# PoE_Si3404.net
KiCad netlist of a schematic drawn in Altium Designer
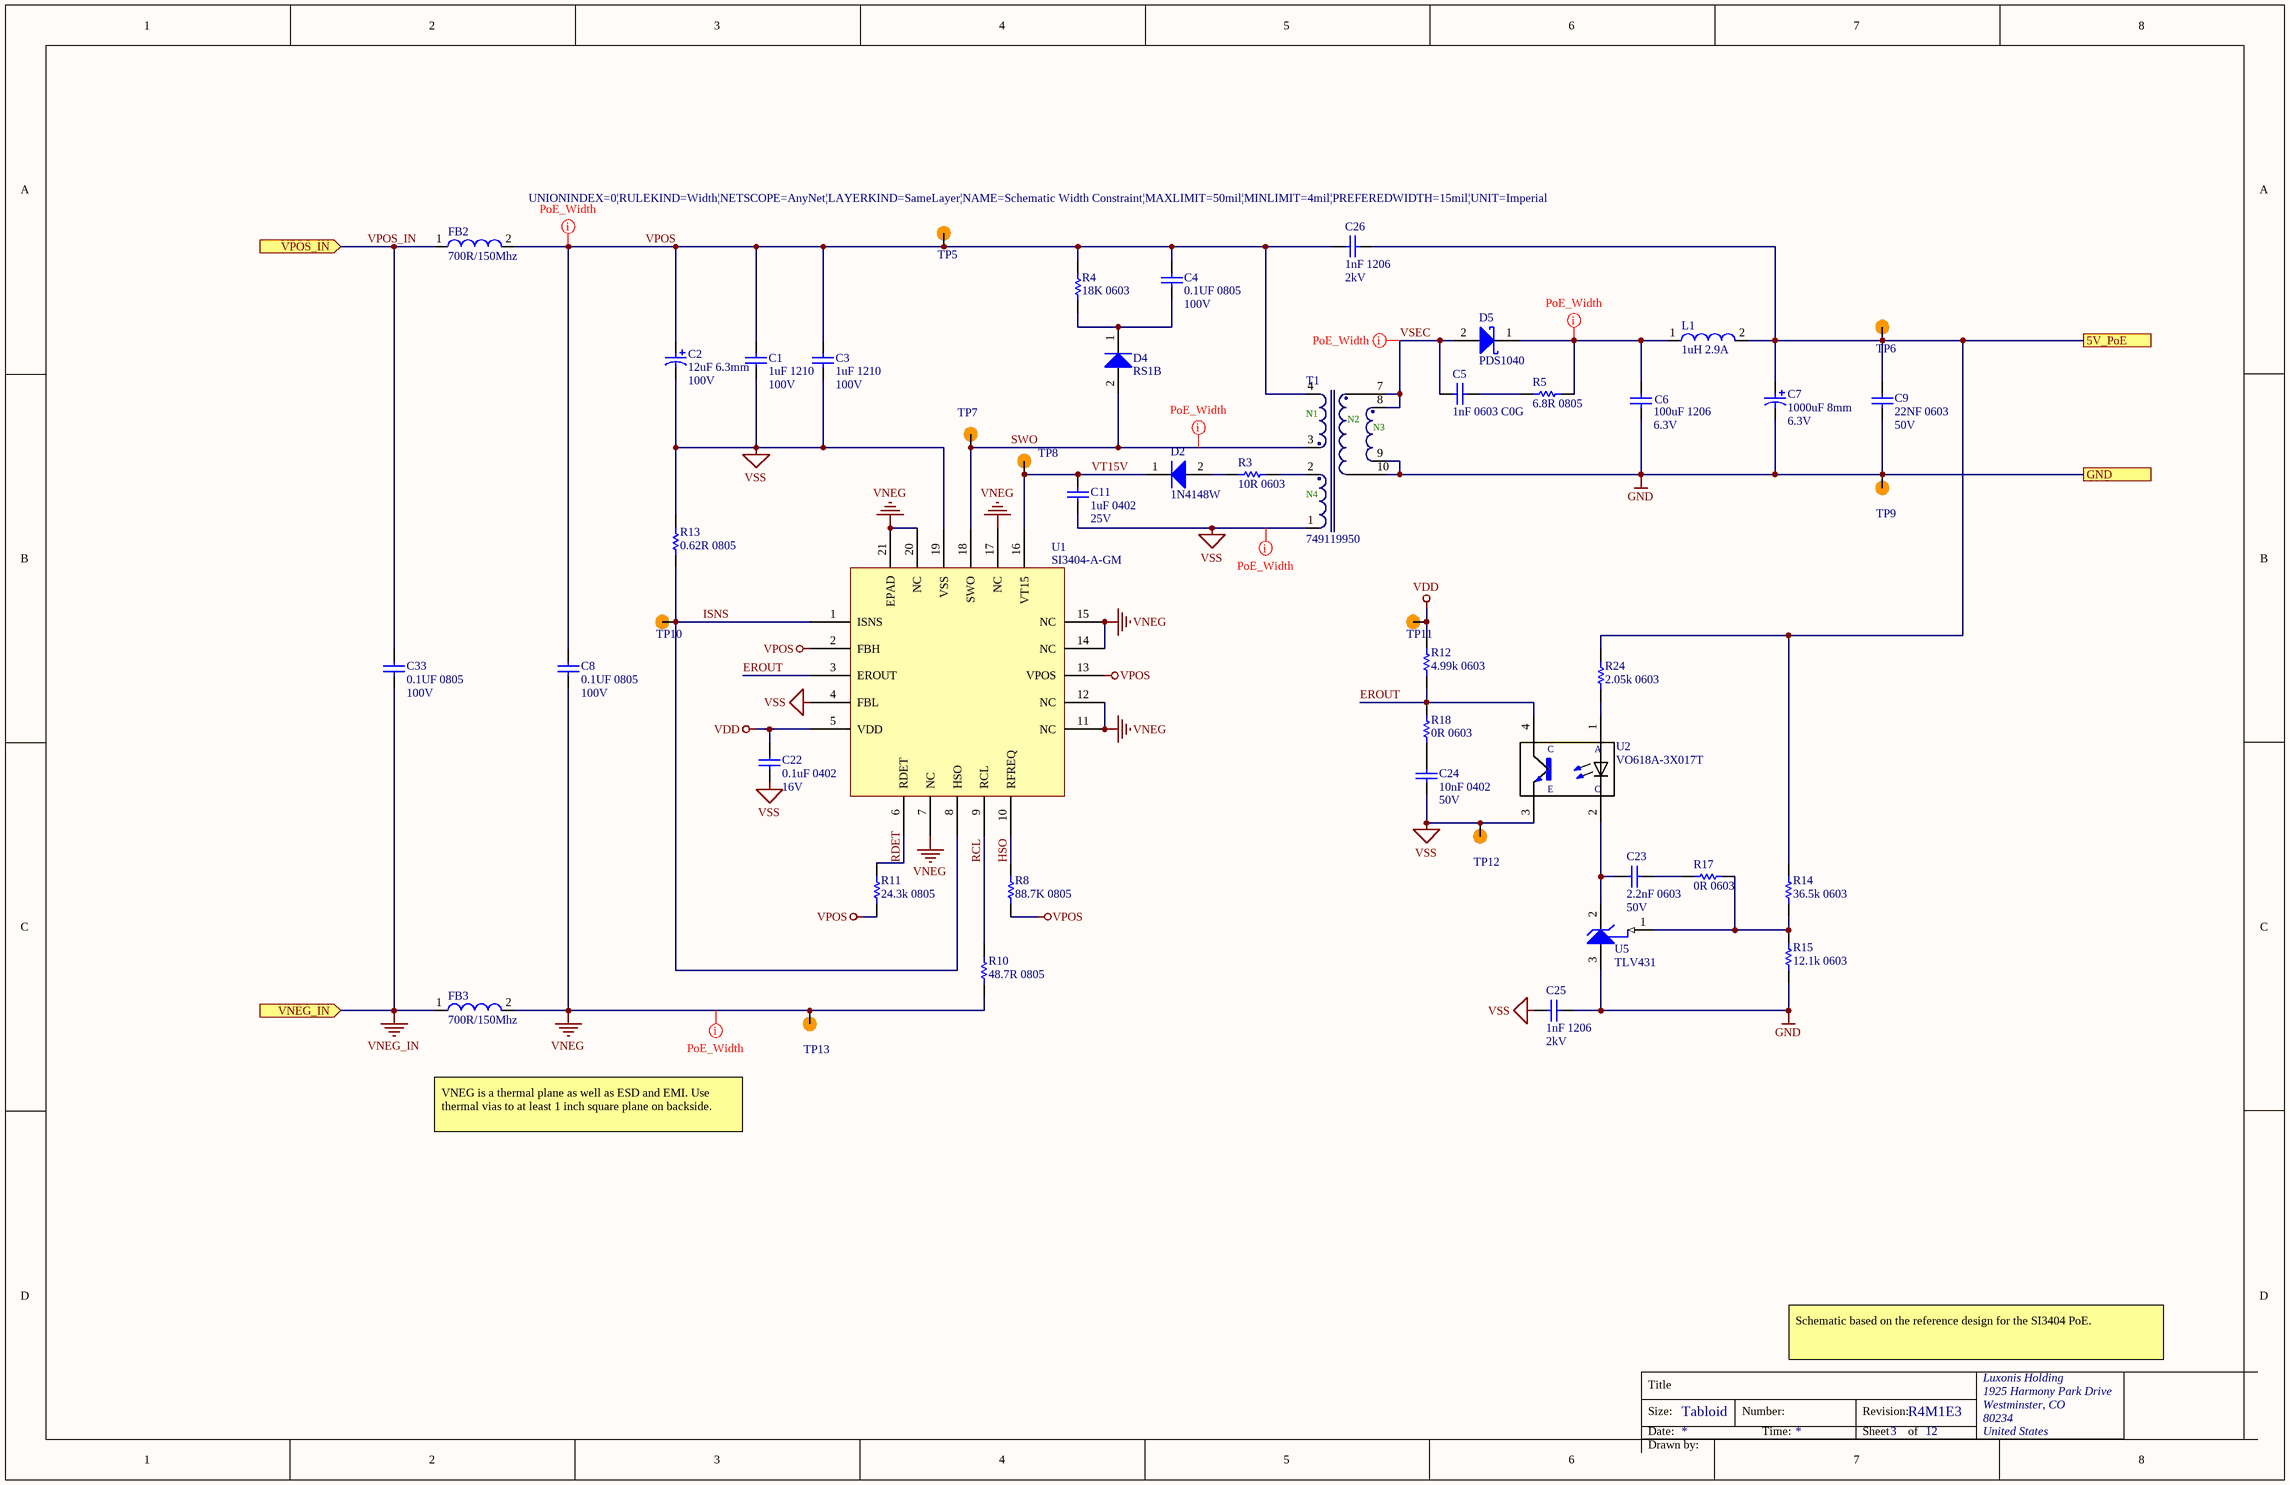
[diagram p0: PoE_Si3404.SchDoc]

(export (version "E")
  (design (tool "Eeschema 10.0.6"))
  (components
    (comp (ref "C1")
      (value "1uF 1210")
      (footprint "CAP_Altium_Vault_Generic:CAPC1210(3225)280_N")
      (description "CAP CER 1UF 100V X7R 1210")
      (fields (field (name "TOLERANCE") "10%") (field (name "VOLTAGE RATING") "100V"))
      (libsource (lib "PCBProject") (part "CL32B105KCJNNNE"))
    )
    (comp (ref "C2")
      (value "12uF 6.3mm")
      (footprint "BW2098POE:EEU-FC2A120")
      (description "CAP ALUM 12UF 20% 100V RADIAL")
      (fields (field (name "TOLERANCE") "20%") (field (name "VOLTAGE") "100V"))
      (libsource (lib "BW2098POE") (part "EEU-FC2A120"))
    )
    (comp (ref "C3")
      (value "1uF 1210")
      (footprint "CAP_Altium_Vault_Generic:CAPC1210(3225)280_N")
      (description "CAP CER 1UF 100V X7R 1210")
      (fields (field (name "TOLERANCE") "10%") (field (name "VOLTAGE RATING") "100V"))
      (libsource (lib "PCBProject") (part "CL32B105KCJNNNE"))
    )
    (comp (ref "C4")
      (value "0.1UF 0805")
      (footprint "CAP_Altium_Vault_Generic:CAPC0805(2012)145_N")
      (description "CAP CER 0.1UF 100V X7R 0805")
      (fields (field (name "TOLERANCE") "10%") (field (name "VOLTAGE RATING") "100V"))
      (libsource (lib "BW2098POE") (part "CL21B104KCFNNNE"))
    )
    (comp (ref "C5")
      (value "1nF 0603 C0G")
      (footprint "CAP_Altium_Vault_Generic:CAPC0603(1608)100_N")
      (description "CAP CER 1000PF 50V C0G/NP0 0603")
      (fields
        (field (name "MANUFACTURER") "Murata")
        (field (name "MANUFACTURER PART NUMBER") "GRM1885C1H102FA01D")
      )
      (libsource (lib "LuxonisMaster") (part "GRM1885C1H102FA01D"))
    )
    (comp (ref "C6")
      (value "100uF 1206")
      (footprint "CAP_Altium_Vault_Generic:CAPC1206(3216)190_N")
      (description "CAP CER 100UF 6.3V X5R 1206")
      (fields (field (name "TOLERANCE") "20%") (field (name "VOLTAGE") "6.3V"))
      (libsource (lib "PCBProject") (part "CL31A107MQHNNNE"))
    )
    (comp (ref "C7")
      (value "1000uF 8mm")
      (footprint "BW2098POE:ECA-0JM102")
      (description "CAP ALUM 1000UF 20% 6.3V RADIAL")
      (fields (field (name "TOLERANCE") "20%") (field (name "VOLTAGE") "6.3V"))
      (libsource (lib "BW2098POE") (part "ECA-0JM102"))
    )
    (comp (ref "C8")
      (value "0.1UF 0805")
      (footprint "CAP_Altium_Vault_Generic:CAPC0805(2012)145_N")
      (description "CAP CER 0.1UF 100V X7R 0805")
      (fields (field (name "TOLERANCE") "10%") (field (name "VOLTAGE RATING") "100V"))
      (libsource (lib "PCBProject") (part "CL21B104KCFNNNE"))
    )
    (comp (ref "C9")
      (value "22NF 0603")
      (footprint "CAP_Altium_Vault_Generic:CAPC0603(1608)100_N")
      (description "CAP CER 0.022UF 50V X7R 0603")
      (fields (field (name "TOLERANCE") "10%") (field (name "VOLTAGE") "50V"))
      (libsource (lib "LuxonisMaster") (part "C0603C223K5RACTU"))
    )
    (comp (ref "C11")
      (value "1uF 0402")
      (footprint "CAP_Altium_Vault_Generic:CAPC0402(1005)70_N")
      (description "CAP CER 1UF 25V X5R 0402 10%")
      (fields
        (field (name "TOLERANCE") "10%")
        (field (name "VOLTAGE") "25V")
        (field (name "VOLTAGE RATING") "25V")
      )
      (libsource (lib "LuxonisMaster") (part "GRM155R61E105KA12D"))
    )
    (comp (ref "C22")
      (value "0.1uF 0402")
      (footprint "CAP_Altium_Vault_Generic:CAPC0402(1005)60_N")
      (description "CAP CER 0.1UF 16V X7R 0402")
      (fields (field (name "TOLERANCE") "10%") (field (name "VOLTAGE RATING") "16V"))
      (libsource (lib "PCBProject") (part "CL05B104KO5NFNC"))
    )
    (comp (ref "C23")
      (value "2.2nF 0603")
      (footprint "CAP_Altium_Vault_Generic:CAPC0603(1608)100_N")
      (description "CAP CER 2200PF 50V C0G/NP0 0603")
      (fields (field (name "TOLERANCE") "5%") (field (name "VOLTAGE") "50V"))
      (libsource (lib "BW2098POE") (part "GRM1885C1H222JA01D"))
    )
    (comp (ref "C24")
      (value "10nF 0402")
      (footprint "CAP_Altium_Vault_Generic:CAPC0402(1005)60_N")
      (description "CAP CER 10000PF 50V X7R 0402")
      (fields
        (field (name "TOLERANCE") "10%")
        (field (name "VOLTAGE") "25V")
        (field (name "VOLTAGE RATING") "50V")
      )
      (libsource (lib "LuxonisMaster") (part "GRM155R71H103KA88D"))
    )
    (comp (ref "C25")
      (value "1nF 1206")
      (footprint "CAP_Altium_Vault_Generic:CAPC1206(3216)190_N")
      (description "CAP CER 1000PF 2KV X7R 1206")
      (fields (field (name "TOLERANCE") "10%") (field (name "VOLTAGE RATING (DC)") "2kV"))
      (libsource (lib "PCBProject") (part "C1206C102KGRACTU"))
    )
    (comp (ref "C26")
      (value "1nF 1206")
      (footprint "CAP_Altium_Vault_Generic:CAPC1206(3216)190_N")
      (description "CAP CER 1000PF 2KV X7R 1206")
      (fields (field (name "TOLERANCE") "10%") (field (name "VOLTAGE RATING (DC)") "2kV"))
      (libsource (lib "PCBProject") (part "C1206C102KGRACTU"))
    )
    (comp (ref "C33")
      (value "0.1UF 0805")
      (footprint "CAP_Altium_Vault_Generic:CAPC0805(2012)145_N")
      (description "CAP CER 0.1UF 100V X7R 0805")
      (fields (field (name "TOLERANCE") "10%") (field (name "VOLTAGE RATING") "100V"))
      (libsource (lib "PCBProject") (part "CL21B104KCFNNNE"))
    )
    (comp (ref "D2")
      (value "1N4148W")
      (footprint "BW2098POE:1N4148W-7-F")
      (description "DIODE GEN PURP 100V 300MA SOD123")
      (fields (field (name "VOLTAGE") "100V"))
      (libsource (lib "PCBProject") (part "1N4148W-7-F"))
    )
    (comp (ref "D4")
      (value "RS1B")
      (footprint "BW2098POE:RS1B")
      (description "DIODE GEN PURP 100V 1A SMA")
      (libsource (lib "BW2098POE") (part "RS1B"))
    )
    (comp (ref "D5")
      (value "PDS1040")
      (footprint "BW2098POE:PDS1040-13")
      (description "DIODE SCHOTTKY 40V 10A POWERDI5")
      (libsource (lib "PCBProject") (part "PDS1040-13"))
    )
    (comp (ref "FB2")
      (value "700R/150Mhz")
      (footprint "BW2098POE:742792040")
      (description "FERRITE BEAD 600 OHM 0805 1LN")
      (fields (field (name "TOLERANCE") "25%"))
      (libsource (lib "BW2098POE") (part "742792040"))
    )
    (comp (ref "FB3")
      (value "700R/150Mhz")
      (footprint "BW2098POE:742792040")
      (description "FERRITE BEAD 600 OHM 0805 1LN")
      (fields (field (name "TOLERANCE") "25%"))
      (libsource (lib "BW2098POE") (part "742792040"))
    )
    (comp (ref "L1")
      (value "1uH 2.9A")
      (footprint "BW2098POE:DO1608C-102MLx")
      (description "IND POWER WIREWOUND 1uH 20% 100KHz FERRITE 2.7A")
      (fields (field (name "TOLERANCE") "20%"))
      (libsource (lib "PCBProject") (part "DO1608C-102ML"))
    )
    (comp (ref "R3")
      (value "10R 0603")
      (footprint "RES_Altium_Vault_Generic:RESC0603(1608)_N")
      (description "RES SMD 10 OHM 1% 1/10W 0603")
      (fields (field (name "TOLERANCE") "1%"))
      (libsource (lib "PCBProject") (part "CRCW060310R0FKEA"))
    )
    (comp (ref "R4")
      (value "18K 0603")
      (footprint "RES_Altium_Vault_Generic:RESC0603(1608)_N")
      (description "RES SMD 18K OHM 5% 1/10W 0603")
      (fields (field (name "TOLERANCE") "5%"))
      (libsource (lib "BW2098POE") (part "RC0603JR-0718KL"))
    )
    (comp (ref "R5")
      (value "6.8R 0805")
      (footprint "RES_Altium_Vault_Generic:RESC0805(2012)_N")
      (description "RES SMD 6.8 OHM 1% 1/8W 0805")
      (fields (field (name "TOLERANCE") "1%"))
      (libsource (lib "BW2098POE") (part "RC0805FR-076R8L"))
    )
    (comp (ref "R8")
      (value "88.7K 0805")
      (footprint "RES_Altium_Vault_Generic:RESC0805(2012)_N")
      (description "RES SMD 88.7K OHM 1% 1/8W 0805")
      (fields (field (name "TOLERANCE") "1%"))
      (libsource (lib "BW2098POE") (part "CRCW080588K7FKEA"))
    )
    (comp (ref "R10")
      (value "48.7R 0805")
      (footprint "RES_Altium_Vault_Generic:RESC0805(2012)_N")
      (description "RES SMD 48.7 OHM 1% 1/8W 0805")
      (fields (field (name "TOLERANCE") "1%"))
      (libsource (lib "PCBProject") (part "RC0805FR-0748R7L"))
    )
    (comp (ref "R11")
      (value "24.3k 0805")
      (footprint "RES_Altium_Vault_Generic:RESC0805(2012)_N")
      (description "RES SMD 24.3K OHM 1% 1/8W 0805")
      (fields (field (name "TOLERANCE") "1%"))
      (libsource (lib "PCBProject") (part "CRCW080524K3FKEA"))
    )
    (comp (ref "R12")
      (value "4.99k 0603")
      (footprint "RES_Altium_Vault_Generic:RESC0603(1608)_N")
      (description "RES SMD 4.99K OHM 1% 1/10W 0603")
      (fields (field (name "TOLERANCE") "1%"))
      (libsource (lib "PCBProject") (part "RC0603FR-074K99L"))
    )
    (comp (ref "R13")
      (value "0.62R 0805")
      (footprint "RES_Altium_Vault_Generic:RESC0805(2012)_N")
      (description "RES SMD 620 MOHM 1% 1/8W 0805")
      (fields (field (name "TOLERANCE") "1%"))
      (libsource (lib "BW2098POE") (part "RL0805FR-070R62L"))
    )
    (comp (ref "R14")
      (value "36.5k 0603")
      (footprint "RES_Altium_Vault_Generic:RESC0603(1608)_N")
      (description "RES SMD 36.5K OHM 1% 1/10W 0603")
      (fields (field (name "TOLERANCE") "1%"))
      (libsource (lib "PCBProject") (part "RC0603FR-0736K5L"))
    )
    (comp (ref "R15")
      (value "12.1k 0603")
      (footprint "RES_Altium_Vault_Generic:RESC0603(1608)_N")
      (description "RES SMD 12.1K OHM 1% 1/10W 0603")
      (fields (field (name "TOLERANCE") "1%"))
      (libsource (lib "PCBProject") (part "RC0603FR-0712K1L"))
    )
    (comp (ref "R17")
      (value "0R 0603")
      (footprint "RES_Altium_Vault_Generic:RESC0603(1608)_N")
      (fields (field (name "TOLERANCE") "5%"))
      (libsource (lib "LuxonisMaster") (part "CRCW06030000Z0EA"))
    )
    (comp (ref "R18")
      (value "0R 0603")
      (footprint "RES_Altium_Vault_Generic:RESC0603(1608)_N")
      (fields (field (name "TOLERANCE") "5%"))
      (libsource (lib "LuxonisMaster") (part "CRCW06030000Z0EA"))
    )
    (comp (ref "R24")
      (value "2.05k 0603")
      (footprint "RES_Altium_Vault_Generic:RESC0603(1608)_N")
      (description "RES SMD 2.05K OHM 1% 1/10W 0603")
      (fields (field (name "TOLERANCE") "1%"))
      (libsource (lib "PCBProject") (part "RC0603FR-072K05L"))
    )
    (comp (ref "T1")
      (value "749119950")
      (footprint "BW2098POE:749119950")
      (description "TRANS FLYBACK POE 127UH SMD")
      (libsource (lib "BW2098POE") (part "749119950"))
    )
    (comp (ref "TP5")
      (value "TP100_200_NS")
      (footprint "LuxonisMaster:TP100_200_NS")
      (libsource (lib "LuxonisMaster") (part "TEST_POINT"))
    )
    (comp (ref "TP6")
      (value "TP100_200_NS")
      (footprint "LuxonisMaster:TP100_200_NS")
      (libsource (lib "LuxonisMaster") (part "TEST_POINT"))
    )
    (comp (ref "TP7")
      (value "TP100_200_NS")
      (footprint "LuxonisMaster:TP100_200_NS")
      (libsource (lib "LuxonisMaster") (part "TEST_POINT"))
    )
    (comp (ref "TP8")
      (value "TP100_200_NS")
      (footprint "LuxonisMaster:TP100_200_NS")
      (libsource (lib "LuxonisMaster") (part "TEST_POINT"))
    )
    (comp (ref "TP9")
      (value "TP100_200_NS")
      (footprint "LuxonisMaster:TP100_200_NS")
      (libsource (lib "LuxonisMaster") (part "TEST_POINT"))
    )
    (comp (ref "TP10")
      (value "TP100_200_NS")
      (footprint "LuxonisMaster:TP100_200_NS")
      (libsource (lib "LuxonisMaster") (part "TEST_POINT"))
    )
    (comp (ref "TP11")
      (value "TP100_200_NS")
      (footprint "LuxonisMaster:TP100_200_NS")
      (libsource (lib "LuxonisMaster") (part "TEST_POINT"))
    )
    (comp (ref "TP12")
      (value "TP100_200_NS")
      (footprint "LuxonisMaster:TP100_200_NS")
      (libsource (lib "LuxonisMaster") (part "TEST_POINT"))
    )
    (comp (ref "TP13")
      (value "TP100_200_NS")
      (footprint "LuxonisMaster:TP100_200_NS")
      (libsource (lib "LuxonisMaster") (part "TEST_POINT"))
    )
    (comp (ref "U1")
      (value "SI3404-A-GM")
      (footprint "BW2098POE:Si3404-A-GM")
      (description "IC POE CNTRL 1 CHANNEL 20QFN")
      (libsource (lib "BW2098POE") (part "SI3404-A-GM"))
    )
    (comp (ref "U2")
      (value "VO618A-3X017T")
      (footprint "BW2098POE:VO618A-3X017T")
      (description "OPTOISOLATOR 5.3KV TRANS 4-SMD")
      (libsource (lib "BW2098POE") (part "VO618A-3X017T"))
    )
    (comp (ref "U5")
      (value "TLV431")
      (footprint "BW2098POE:TLV431BCDBZR")
      (description "IC VREF SHUNT ADJ SOT23-3")
      (fields (field (name "TOLERANCE") "0.5%"))
      (libsource (lib "BW2098POE") (part "TLV431BCDBZR"))
    )
  )
  (nets
    (net (code "1") (name "/5V_PoE") (class "Default")
      (node (ref "C26") (pin "2") (pinfunction "2_2") (pintype "passive"))
      (node (ref "C7") (pin "1") (pinfunction "1_1") (pintype "passive"))
      (node (ref "C9") (pin "2") (pinfunction "2_2") (pintype "passive"))
      (node (ref "L1") (pin "2") (pinfunction "2_2") (pintype "passive"))
      (node (ref "R14") (pin "2") (pinfunction "2_2") (pintype "passive"))
      (node (ref "R24") (pin "2") (pinfunction "2_2") (pintype "passive"))
      (node (ref "TP6") (pin "1") (pintype "passive"))
    )
    (net (code "2") (name "/EROUT") (class "Default")
      (node (ref "R12") (pin "1") (pinfunction "1_1") (pintype "passive"))
      (node (ref "R18") (pin "2") (pinfunction "2_2") (pintype "passive"))
      (node (ref "U1") (pin "3") (pinfunction "EROUT_3") (pintype "passive"))
      (node (ref "U2") (pin "4") (pinfunction "CO_4") (pintype "passive"))
    )
    (net (code "3") (name "/HSO") (class "Default")
      (node (ref "R8") (pin "2") (pinfunction "2_2") (pintype "passive"))
      (node (ref "U1") (pin "10") (pinfunction "RFREQ_10") (pintype "passive"))
    )
    (net (code "4") (name "/ISNS") (class "Default")
      (node (ref "R13") (pin "1") (pinfunction "1_1") (pintype "passive"))
      (node (ref "TP10") (pin "1") (pintype "passive"))
      (node (ref "U1") (pin "1") (pinfunction "ISNS_1") (pintype "passive"))
      (node (ref "U1") (pin "8") (pinfunction "HSO_8") (pintype "passive"))
    )
    (net (code "5") (name "/RCL") (class "Default")
      (node (ref "R10") (pin "2") (pinfunction "2_2") (pintype "passive"))
      (node (ref "U1") (pin "9") (pinfunction "RCL_9") (pintype "passive"))
    )
    (net (code "6") (name "/RDET") (class "Default")
      (node (ref "R11") (pin "2") (pinfunction "2_2") (pintype "passive"))
      (node (ref "U1") (pin "6") (pinfunction "RDET_6") (pintype "passive"))
    )
    (net (code "7") (name "/SWO") (class "Default")
      (node (ref "D4") (pin "2") (pinfunction "A_2") (pintype "passive"))
      (node (ref "T1") (pin "3") (pinfunction "3_3") (pintype "passive"))
      (node (ref "TP7") (pin "1") (pintype "passive"))
      (node (ref "U1") (pin "18") (pinfunction "SWO_18") (pintype "passive"))
    )
    (net (code "8") (name "/VPOS_IN") (class "Default")
      (node (ref "C33") (pin "2") (pinfunction "2_2") (pintype "passive"))
      (node (ref "FB2") (pin "1") (pinfunction "1_1") (pintype "passive"))
    )
    (net (code "9") (name "/VSEC") (class "Default")
      (node (ref "C5") (pin "2") (pinfunction "2_2") (pintype "passive"))
      (node (ref "D5") (pin "2") (pinfunction "A_2") (pintype "passive"))
      (node (ref "T1") (pin "7") (pinfunction "7_7") (pintype "passive"))
      (node (ref "T1") (pin "8") (pinfunction "8_8") (pintype "passive"))
    )
    (net (code "10") (name "/VT15V") (class "Default")
      (node (ref "C11") (pin "2") (pinfunction "2_2") (pintype "passive"))
      (node (ref "D2") (pin "1") (pinfunction "K_1") (pintype "passive"))
      (node (ref "TP8") (pin "1") (pintype "passive"))
      (node (ref "U1") (pin "16") (pinfunction "VT15_16") (pintype "passive"))
    )
    (net (code "11") (name "GND") (class "Default")
      (node (ref "C25") (pin "2") (pinfunction "2_2") (pintype "passive"))
      (node (ref "C6") (pin "1") (pinfunction "1_1") (pintype "passive"))
      (node (ref "C7") (pin "2") (pinfunction "2_2") (pintype "passive"))
      (node (ref "C9") (pin "1") (pinfunction "1_1") (pintype "passive"))
      (node (ref "R15") (pin "1") (pinfunction "1_1") (pintype "passive"))
      (node (ref "T1") (pin "10") (pinfunction "10_10") (pintype "passive"))
      (node (ref "T1") (pin "9") (pinfunction "9_9") (pintype "passive"))
      (node (ref "TP9") (pin "1") (pintype "passive"))
      (node (ref "U5") (pin "3") (pinfunction "ANODE_3") (pintype "passive"))
    )
    (net (code "12") (name "Net-(C5-Pad1)") (class "Default")
      (node (ref "C5") (pin "1") (pinfunction "1_1") (pintype "passive"))
      (node (ref "R5") (pin "1") (pinfunction "1_1") (pintype "passive"))
    )
    (net (code "13") (name "Net-(C23-Pad2)") (class "Default")
      (node (ref "C23") (pin "2") (pinfunction "2_2") (pintype "passive"))
      (node (ref "R17") (pin "2") (pinfunction "2_2") (pintype "passive"))
    )
    (net (code "14") (name "Net-(C24-Pad2)") (class "Default")
      (node (ref "C24") (pin "2") (pinfunction "2_2") (pintype "passive"))
      (node (ref "R18") (pin "1") (pinfunction "1_1") (pintype "passive"))
    )
    (net (code "15") (name "Net-(D2-A)") (class "Default")
      (node (ref "D2") (pin "2") (pinfunction "A_2") (pintype "passive"))
      (node (ref "R3") (pin "1") (pinfunction "1_1") (pintype "passive"))
    )
    (net (code "16") (name "Net-(D4-K)") (class "Default")
      (node (ref "C4") (pin "1") (pinfunction "1_1") (pintype "passive"))
      (node (ref "D4") (pin "1") (pinfunction "K_1") (pintype "passive"))
      (node (ref "R4") (pin "1") (pinfunction "1_1") (pintype "passive"))
    )
    (net (code "17") (name "Net-(D5-K)") (class "Default")
      (node (ref "C6") (pin "2") (pinfunction "2_2") (pintype "passive"))
      (node (ref "D5") (pin "1") (pinfunction "K_1") (pintype "passive"))
      (node (ref "L1") (pin "1") (pinfunction "1_1") (pintype "passive"))
      (node (ref "R5") (pin "2") (pinfunction "2_2") (pintype "passive"))
    )
    (net (code "18") (name "Net-(R3-Pad2)") (class "Default")
      (node (ref "R3") (pin "2") (pinfunction "2_2") (pintype "passive"))
      (node (ref "T1") (pin "2") (pinfunction "2_2") (pintype "passive"))
    )
    (net (code "19") (name "Net-(U2-A)") (class "Default")
      (node (ref "R24") (pin "1") (pinfunction "1_1") (pintype "passive"))
      (node (ref "U2") (pin "1") (pinfunction "A_1") (pintype "passive"))
    )
    (net (code "20") (name "Net-(U2-C)") (class "Default")
      (node (ref "C23") (pin "1") (pinfunction "1_1") (pintype "passive"))
      (node (ref "U2") (pin "2") (pinfunction "C_2") (pintype "passive"))
      (node (ref "U5") (pin "2") (pinfunction "CATHODE_2") (pintype "passive"))
    )
    (net (code "21") (name "Net-(U5-REF)") (class "Default")
      (node (ref "R14") (pin "1") (pinfunction "1_1") (pintype "passive"))
      (node (ref "R15") (pin "2") (pinfunction "2_2") (pintype "passive"))
      (node (ref "R17") (pin "1") (pinfunction "1_1") (pintype "passive"))
      (node (ref "U5") (pin "1") (pinfunction "REF_1") (pintype "input"))
    )
    (net (code "22") (name "VDD") (class "Default")
      (node (ref "C22") (pin "2") (pinfunction "2_2") (pintype "passive"))
      (node (ref "R12") (pin "2") (pinfunction "2_2") (pintype "passive"))
      (node (ref "TP11") (pin "1") (pintype "passive"))
      (node (ref "U1") (pin "5") (pinfunction "VDD_5") (pintype "passive"))
    )
    (net (code "23") (name "VNEG") (class "Default")
      (node (ref "C8") (pin "1") (pinfunction "1_1") (pintype "passive"))
      (node (ref "FB3") (pin "2") (pinfunction "2_2") (pintype "passive"))
      (node (ref "R10") (pin "1") (pinfunction "1_1") (pintype "passive"))
      (node (ref "TP13") (pin "1") (pintype "passive"))
      (node (ref "U1") (pin "11") (pinfunction "NC_11") (pintype "passive"))
      (node (ref "U1") (pin "12") (pinfunction "NC_12") (pintype "passive"))
      (node (ref "U1") (pin "14") (pinfunction "NC_14") (pintype "passive"))
      (node (ref "U1") (pin "15") (pinfunction "NC_15") (pintype "passive"))
      (node (ref "U1") (pin "17") (pinfunction "NC_17") (pintype "passive"))
      (node (ref "U1") (pin "20") (pinfunction "NC_20") (pintype "passive"))
      (node (ref "U1") (pin "21") (pinfunction "EPAD_21") (pintype "passive"))
      (node (ref "U1") (pin "7") (pinfunction "NC_7") (pintype "passive"))
    )
    (net (code "24") (name "VNEG_IN") (class "Default")
      (node (ref "C33") (pin "1") (pinfunction "1_1") (pintype "passive"))
      (node (ref "FB3") (pin "1") (pinfunction "1_1") (pintype "passive"))
    )
    (net (code "25") (name "VPOS") (class "Default")
      (node (ref "C1") (pin "2") (pinfunction "2_2") (pintype "passive"))
      (node (ref "C2") (pin "1") (pinfunction "1_1") (pintype "passive"))
      (node (ref "C26") (pin "1") (pinfunction "1_1") (pintype "passive"))
      (node (ref "C3") (pin "2") (pinfunction "2_2") (pintype "passive"))
      (node (ref "C4") (pin "2") (pinfunction "2_2") (pintype "passive"))
      (node (ref "C8") (pin "2") (pinfunction "2_2") (pintype "passive"))
      (node (ref "FB2") (pin "2") (pinfunction "2_2") (pintype "passive"))
      (node (ref "R11") (pin "1") (pinfunction "1_1") (pintype "passive"))
      (node (ref "R4") (pin "2") (pinfunction "2_2") (pintype "passive"))
      (node (ref "R8") (pin "1") (pinfunction "1_1") (pintype "passive"))
      (node (ref "T1") (pin "4") (pinfunction "4_4") (pintype "passive"))
      (node (ref "TP5") (pin "1") (pintype "passive"))
      (node (ref "U1") (pin "13") (pinfunction "VPOS_13") (pintype "passive"))
      (node (ref "U1") (pin "2") (pinfunction "FBH_2") (pintype "passive"))
    )
    (net (code "26") (name "VSS") (class "Default")
      (node (ref "C1") (pin "1") (pinfunction "1_1") (pintype "passive"))
      (node (ref "C11") (pin "1") (pinfunction "1_1") (pintype "passive"))
      (node (ref "C2") (pin "2") (pinfunction "2_2") (pintype "passive"))
      (node (ref "C22") (pin "1") (pinfunction "1_1") (pintype "passive"))
      (node (ref "C24") (pin "1") (pinfunction "1_1") (pintype "passive"))
      (node (ref "C25") (pin "1") (pinfunction "1_1") (pintype "passive"))
      (node (ref "C3") (pin "1") (pinfunction "1_1") (pintype "passive"))
      (node (ref "R13") (pin "2") (pinfunction "2_2") (pintype "passive"))
      (node (ref "T1") (pin "1") (pinfunction "1_1") (pintype "passive"))
      (node (ref "TP12") (pin "1") (pintype "passive"))
      (node (ref "U1") (pin "19") (pinfunction "VSS_19") (pintype "passive"))
      (node (ref "U1") (pin "4") (pinfunction "FBL_4") (pintype "passive"))
      (node (ref "U2") (pin "3") (pinfunction "E_3") (pintype "passive"))
    )
  )
)
